# RoverMeter.net
KiCad netlist of a schematic drawn in EAGLE
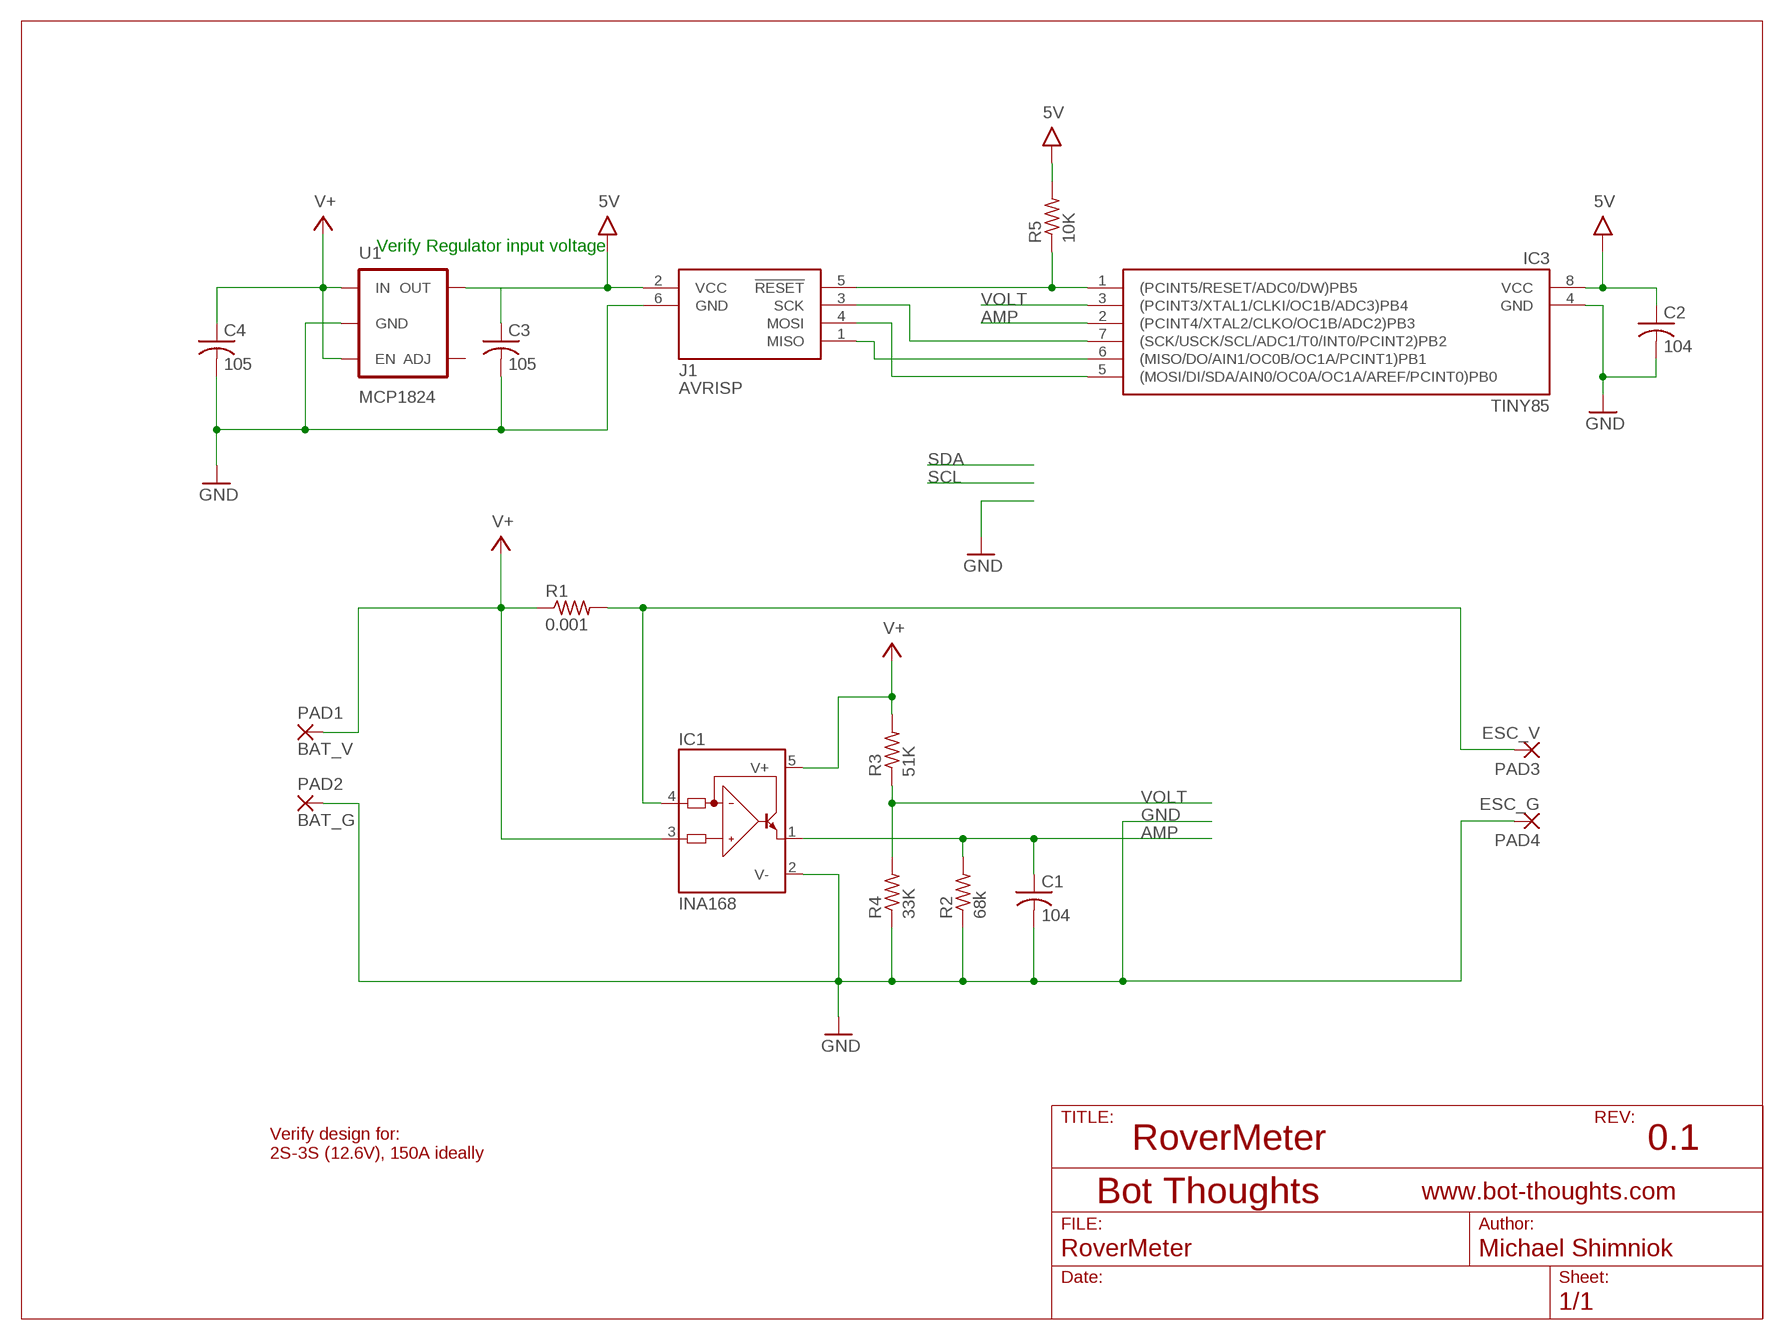
[diagram p0: schematic, sheet 1]

(export (version "E")
  (design (tool "Eeschema 10.0.6"))
  (components
    (comp (ref "C1")
      (value "104")
      (footprint "eagle-import:C0603")
      (libsource (lib "eagle-import") (part "resistor_C-USC0603"))
    )
    (comp (ref "C2")
      (value "104")
      (footprint "eagle-import:C0603")
      (libsource (lib "eagle-import") (part "C-USC0603"))
    )
    (comp (ref "C3")
      (value "105")
      (footprint "eagle-import:C0603")
      (libsource (lib "eagle-import") (part "C-USC0603"))
    )
    (comp (ref "C4")
      (value "105")
      (footprint "eagle-import:C0603")
      (libsource (lib "eagle-import") (part "C-USC0603"))
    )
    (comp (ref "IC1")
      (value "INA168")
      (footprint "eagle-import:SOT23-5")
      (fields (field (name "MF") "TEXAS INSTRUMENTS") (field (name "MPN") "INA168NA/250"))
      (libsource (lib "eagle-import") (part "INA168"))
    )
    (comp (ref "IC3")
      (value "TINY85")
      (footprint "eagle-import:SOIC8")
      (libsource (lib "eagle-import") (part "TINY25/45/85-20SU"))
    )
    (comp (ref "J1")
      (value "AVRISP")
      (footprint "eagle-import:CON6P2R")
      (libsource (lib "eagle-import") (part "AVRISP6"))
    )
    (comp (ref "PAD1")
      (value "BAT_V")
      (footprint "eagle-import:3,81_1,4")
      (libsource (lib "eagle-import") (part "3,81/1,4"))
    )
    (comp (ref "PAD2")
      (value "BAT_G")
      (footprint "eagle-import:3,81_1,4")
      (libsource (lib "eagle-import") (part "3,81/1,4"))
    )
    (comp (ref "PAD3")
      (value "ESC_V")
      (footprint "eagle-import:3,81_1,4")
      (libsource (lib "eagle-import") (part "3,81/1,4"))
    )
    (comp (ref "PAD4")
      (value "ESC_G")
      (footprint "eagle-import:3,81_1,4")
      (libsource (lib "eagle-import") (part "3,81/1,4"))
    )
    (comp (ref "R1")
      (value "0.001")
      (footprint "eagle-import:R4527")
      (libsource (lib "eagle-import") (part "R-US_R4527"))
    )
    (comp (ref "R2")
      (value "68k")
      (footprint "eagle-import:R0603")
      (libsource (lib "eagle-import") (part "R-US_R0603"))
    )
    (comp (ref "R3")
      (value "51K")
      (footprint "eagle-import:R0603")
      (libsource (lib "eagle-import") (part "resistor_R-US_R0603"))
    )
    (comp (ref "R4")
      (value "33K")
      (footprint "eagle-import:R0603")
      (libsource (lib "eagle-import") (part "resistor_R-US_R0603"))
    )
    (comp (ref "R5")
      (value "10K")
      (footprint "eagle-import:R0603")
      (libsource (lib "eagle-import") (part "resistor_R-US_R0603"))
    )
    (comp (ref "U1")
      (value "MCP1824")
      (footprint "eagle-import:SOT23-5")
      (libsource (lib "eagle-import") (part "MCP1824"))
    )
  )
  (nets
    (net (code "1") (name "/AMP") (class "Default")
      (node (ref "C1") (pin "1") (pinfunction "1_1") (pintype "passive"))
      (node (ref "IC1") (pin "1") (pinfunction "OUT_1") (pintype "output"))
      (node (ref "IC3") (pin "2") (pinfunction "(PCINT4/XTAL2/CLKO/OC1B/ADC2)PB3_2") (pintype "bidirectional"))
      (node (ref "R2") (pin "2") (pinfunction "2_2") (pintype "passive"))
    )
    (net (code "2") (name "/SCL") (class "Default")
      (node (ref "IC3") (pin "7") (pinfunction "(SCK/USCK/SCL/ADC1/T0/INT0/PCINT2)PB2_7") (pintype "bidirectional"))
      (node (ref "J1") (pin "3") (pinfunction "SCK_3") (pintype "output"))
    )
    (net (code "3") (name "/SDA") (class "Default")
      (node (ref "IC3") (pin "5") (pinfunction "(MOSI/DI/SDA/AIN0/OC0A/OC1A/AREF/PCINT0)PB0_5") (pintype "bidirectional"))
      (node (ref "J1") (pin "4") (pinfunction "MOSI_4") (pintype "output"))
    )
    (net (code "4") (name "/VOLT") (class "Default")
      (node (ref "IC3") (pin "3") (pinfunction "(PCINT3/XTAL1/CLKI/OC1B/ADC3)PB4_3") (pintype "bidirectional"))
      (node (ref "R3") (pin "1") (pinfunction "1_1") (pintype "passive"))
      (node (ref "R4") (pin "2") (pinfunction "2_2") (pintype "passive"))
    )
    (net (code "5") (name "5V") (class "Default")
      (node (ref "C2") (pin "1") (pinfunction "1_1") (pintype "passive"))
      (node (ref "C3") (pin "1") (pinfunction "1_1") (pintype "passive"))
      (node (ref "IC3") (pin "8") (pinfunction "VCC_8") (pintype "power_in"))
      (node (ref "J1") (pin "2") (pinfunction "VCC_2") (pintype "power_in"))
      (node (ref "R5") (pin "2") (pinfunction "2_2") (pintype "passive"))
      (node (ref "U1") (pin "5") (pinfunction "OUT_5") (pintype "passive"))
    )
    (net (code "6") (name "GND") (class "Default")
      (node (ref "C1") (pin "2") (pinfunction "2_2") (pintype "passive"))
      (node (ref "C2") (pin "2") (pinfunction "2_2") (pintype "passive"))
      (node (ref "C3") (pin "2") (pinfunction "2_2") (pintype "passive"))
      (node (ref "C4") (pin "2") (pinfunction "2_2") (pintype "passive"))
      (node (ref "IC1") (pin "2") (pinfunction "V-_2") (pintype "power_in"))
      (node (ref "IC3") (pin "4") (pinfunction "GND_4") (pintype "power_in"))
      (node (ref "J1") (pin "6") (pinfunction "GND_6") (pintype "power_in"))
      (node (ref "PAD2") (pin "1") (pinfunction "P_1") (pintype "passive"))
      (node (ref "PAD4") (pin "1") (pinfunction "P_1") (pintype "passive"))
      (node (ref "R2") (pin "1") (pinfunction "1_1") (pintype "passive"))
      (node (ref "R4") (pin "1") (pinfunction "1_1") (pintype "passive"))
      (node (ref "U1") (pin "2") (pinfunction "GND_2") (pintype "input"))
    )
    (net (code "7") (name "Net-(IC1-IN-)") (class "Default")
      (node (ref "IC1") (pin "4") (pinfunction "IN-_4") (pintype "input"))
      (node (ref "PAD3") (pin "1") (pinfunction "P_1") (pintype "passive"))
      (node (ref "R1") (pin "2") (pinfunction "2_2") (pintype "passive"))
    )
    (net (code "8") (name "Net-(IC3-(MISO{slash}DO{slash}AIN1{slash}OC0B{slash}OC1A{slash}PCINT1)PB1)") (class "Default")
      (node (ref "IC3") (pin "6") (pinfunction "(MISO/DO/AIN1/OC0B/OC1A/PCINT1)PB1_6") (pintype "bidirectional"))
      (node (ref "J1") (pin "1") (pinfunction "MISO_1") (pintype "input"))
    )
    (net (code "9") (name "Net-(IC3-(PCINT5{slash}RESET{slash}ADC0{slash}DW)PB5)") (class "Default")
      (node (ref "IC3") (pin "1") (pinfunction "(PCINT5/RESET/ADC0/DW)PB5_1") (pintype "bidirectional"))
      (node (ref "J1") (pin "5") (pinfunction "~{RESET}_5") (pintype "output"))
      (node (ref "R5") (pin "1") (pinfunction "1_1") (pintype "passive"))
    )
    (net (code "10") (name "V+") (class "Default")
      (node (ref "C4") (pin "1") (pinfunction "1_1") (pintype "passive"))
      (node (ref "IC1") (pin "3") (pinfunction "IN+_3") (pintype "input"))
      (node (ref "IC1") (pin "5") (pinfunction "V+_5") (pintype "power_in"))
      (node (ref "PAD1") (pin "1") (pinfunction "P_1") (pintype "passive"))
      (node (ref "R1") (pin "1") (pinfunction "1_1") (pintype "passive"))
      (node (ref "R3") (pin "2") (pinfunction "2_2") (pintype "passive"))
      (node (ref "U1") (pin "1") (pinfunction "IN_1") (pintype "input"))
      (node (ref "U1") (pin "3") (pinfunction "EN_3") (pintype "input"))
    )
    (net (code "11") (name "unconnected-(U1-ADJ-Pad4)") (class "Default")
      (node (ref "U1") (pin "4") (pinfunction "ADJ_4") (pintype "input"))
    )
  )
)
